# Sallen_key_LPF.net
KiCad netlist of a schematic drawn in Altium Designer
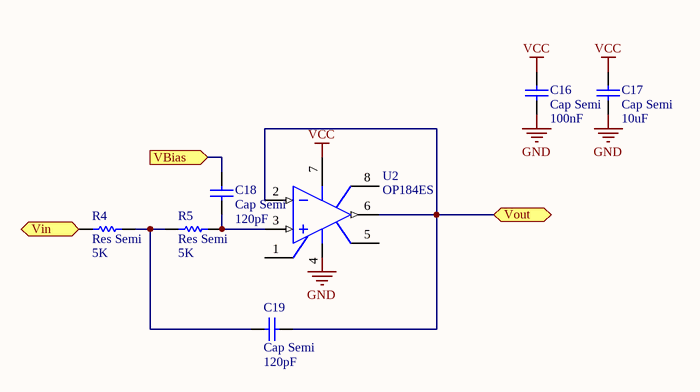
[diagram p0: Sallen_key_LPF.SchDoc]

(export (version "E")
  (design (tool "Eeschema 10.0.6"))
  (components
    (comp (ref "C16")
      (value "Cap Semi")
      (footprint "C0805")
      (description "Capacitor (Semiconductor SIM Model)")
      (fields (field (name "ALTIUM_VALUE") "100nF") (field (name "PUBLISHER") "Altium Limited"))
      (libsource (lib "Miscellaneous Devices") (part "Cap Semi"))
    )
    (comp (ref "C17")
      (value "Cap Semi")
      (footprint "C0805")
      (description "Capacitor (Semiconductor SIM Model)")
      (fields (field (name "ALTIUM_VALUE") "10uF") (field (name "PUBLISHER") "Altium Limited"))
      (libsource (lib "Miscellaneous Devices") (part "Cap Semi"))
    )
    (comp (ref "C18")
      (value "Cap Semi")
      (footprint "C0805")
      (description "Capacitor (Semiconductor SIM Model)")
      (fields (field (name "ALTIUM_VALUE") "120pF") (field (name "PUBLISHER") "Altium Limited"))
      (libsource (lib "Miscellaneous Devices") (part "Cap Semi"))
    )
    (comp (ref "C19")
      (value "Cap Semi")
      (footprint "C0805")
      (description "Capacitor (Semiconductor SIM Model)")
      (fields (field (name "ALTIUM_VALUE") "120pF") (field (name "PUBLISHER") "Altium Limited"))
      (libsource (lib "Miscellaneous Devices") (part "Cap Semi"))
    )
    (comp (ref "R4")
      (value "Res Semi")
      (footprint "RESC2012L")
      (description "Semiconductor Resistor")
      (fields (field (name "ALTIUM_VALUE") "5K") (field (name "PUBLISHER") "Altium Limited"))
      (libsource (lib "Miscellaneous Devices") (part "Res Semi"))
    )
    (comp (ref "R5")
      (value "Res Semi")
      (footprint "RESC2012L")
      (description "Semiconductor Resistor")
      (fields (field (name "ALTIUM_VALUE") "5K") (field (name "PUBLISHER") "Altium Limited"))
      (libsource (lib "Miscellaneous Devices") (part "Res Semi"))
    )
    (comp (ref "U2")
      (value "OP184ES")
      (footprint "SO-8_N")
      (description "Precision Rail-to-Rail Input and Ouput Operational Amplifier")
      (fields (field (name "PUBLISHER") "Altium Limited"))
      (libsource (lib "AD Operational Amplifier") (part "OP184ES"))
    )
  )
  (nets
    (net (code "1") (name "/VBias") (class "Default")
      (node (ref "C18") (pin "2") (pinfunction "2_2") (pintype "passive"))
    )
    (net (code "2") (name "/Vin") (class "Default")
      (node (ref "R4") (pin "1") (pinfunction "1_1") (pintype "passive"))
    )
    (net (code "3") (name "/Vout") (class "Default")
      (node (ref "C19") (pin "1") (pinfunction "1_1") (pintype "passive"))
      (node (ref "U2") (pin "2") (pinfunction "IN-_2") (pintype "input"))
      (node (ref "U2") (pin "6") (pinfunction "OUT_6") (pintype "output"))
    )
    (net (code "4") (name "GND") (class "Default")
      (node (ref "C16") (pin "1") (pinfunction "1_1") (pintype "passive"))
      (node (ref "C17") (pin "1") (pinfunction "1_1") (pintype "passive"))
    )
    (net (code "5") (name "Net-(C19-Pad2)") (class "Default")
      (node (ref "C19") (pin "2") (pinfunction "2_2") (pintype "passive"))
      (node (ref "R4") (pin "2") (pinfunction "2_2") (pintype "passive"))
      (node (ref "R5") (pin "1") (pinfunction "1_1") (pintype "passive"))
    )
    (net (code "6") (name "Net-(U2-IN+)") (class "Default")
      (node (ref "C18") (pin "1") (pinfunction "1_1") (pintype "passive"))
      (node (ref "R5") (pin "2") (pinfunction "2_2") (pintype "passive"))
      (node (ref "U2") (pin "3") (pinfunction "IN+_3") (pintype "input"))
    )
    (net (code "7") (name "VCC") (class "Default")
      (node (ref "C16") (pin "2") (pinfunction "2_2") (pintype "passive"))
      (node (ref "C17") (pin "2") (pinfunction "2_2") (pintype "passive"))
      (node (ref "U2") (pin "7") (pinfunction "V+_7") (pintype "power_in"))
    )
    (net (code "8") (name "unconnected-(U2-NC-Pad8)") (class "Default")
      (node (ref "U2") (pin "8") (pinfunction "NC_8") (pintype "passive"))
    )
    (net (code "9") (name "unconnected-(U2-NUL-Pad1)") (class "Default")
      (node (ref "U2") (pin "1") (pinfunction "NUL_1") (pintype "passive"))
    )
    (net (code "10") (name "unconnected-(U2-NUL-Pad5)") (class "Default")
      (node (ref "U2") (pin "5") (pinfunction "NUL_5") (pintype "passive"))
    )
    (net (code "11") (name "unconnected-(U2-V--Pad4)") (class "Default")
      (node (ref "U2") (pin "4") (pinfunction "V-_4") (pintype "power_in"))
    )
  )
)
